# Swathi.net
KiCad netlist of a schematic drawn in EAGLE
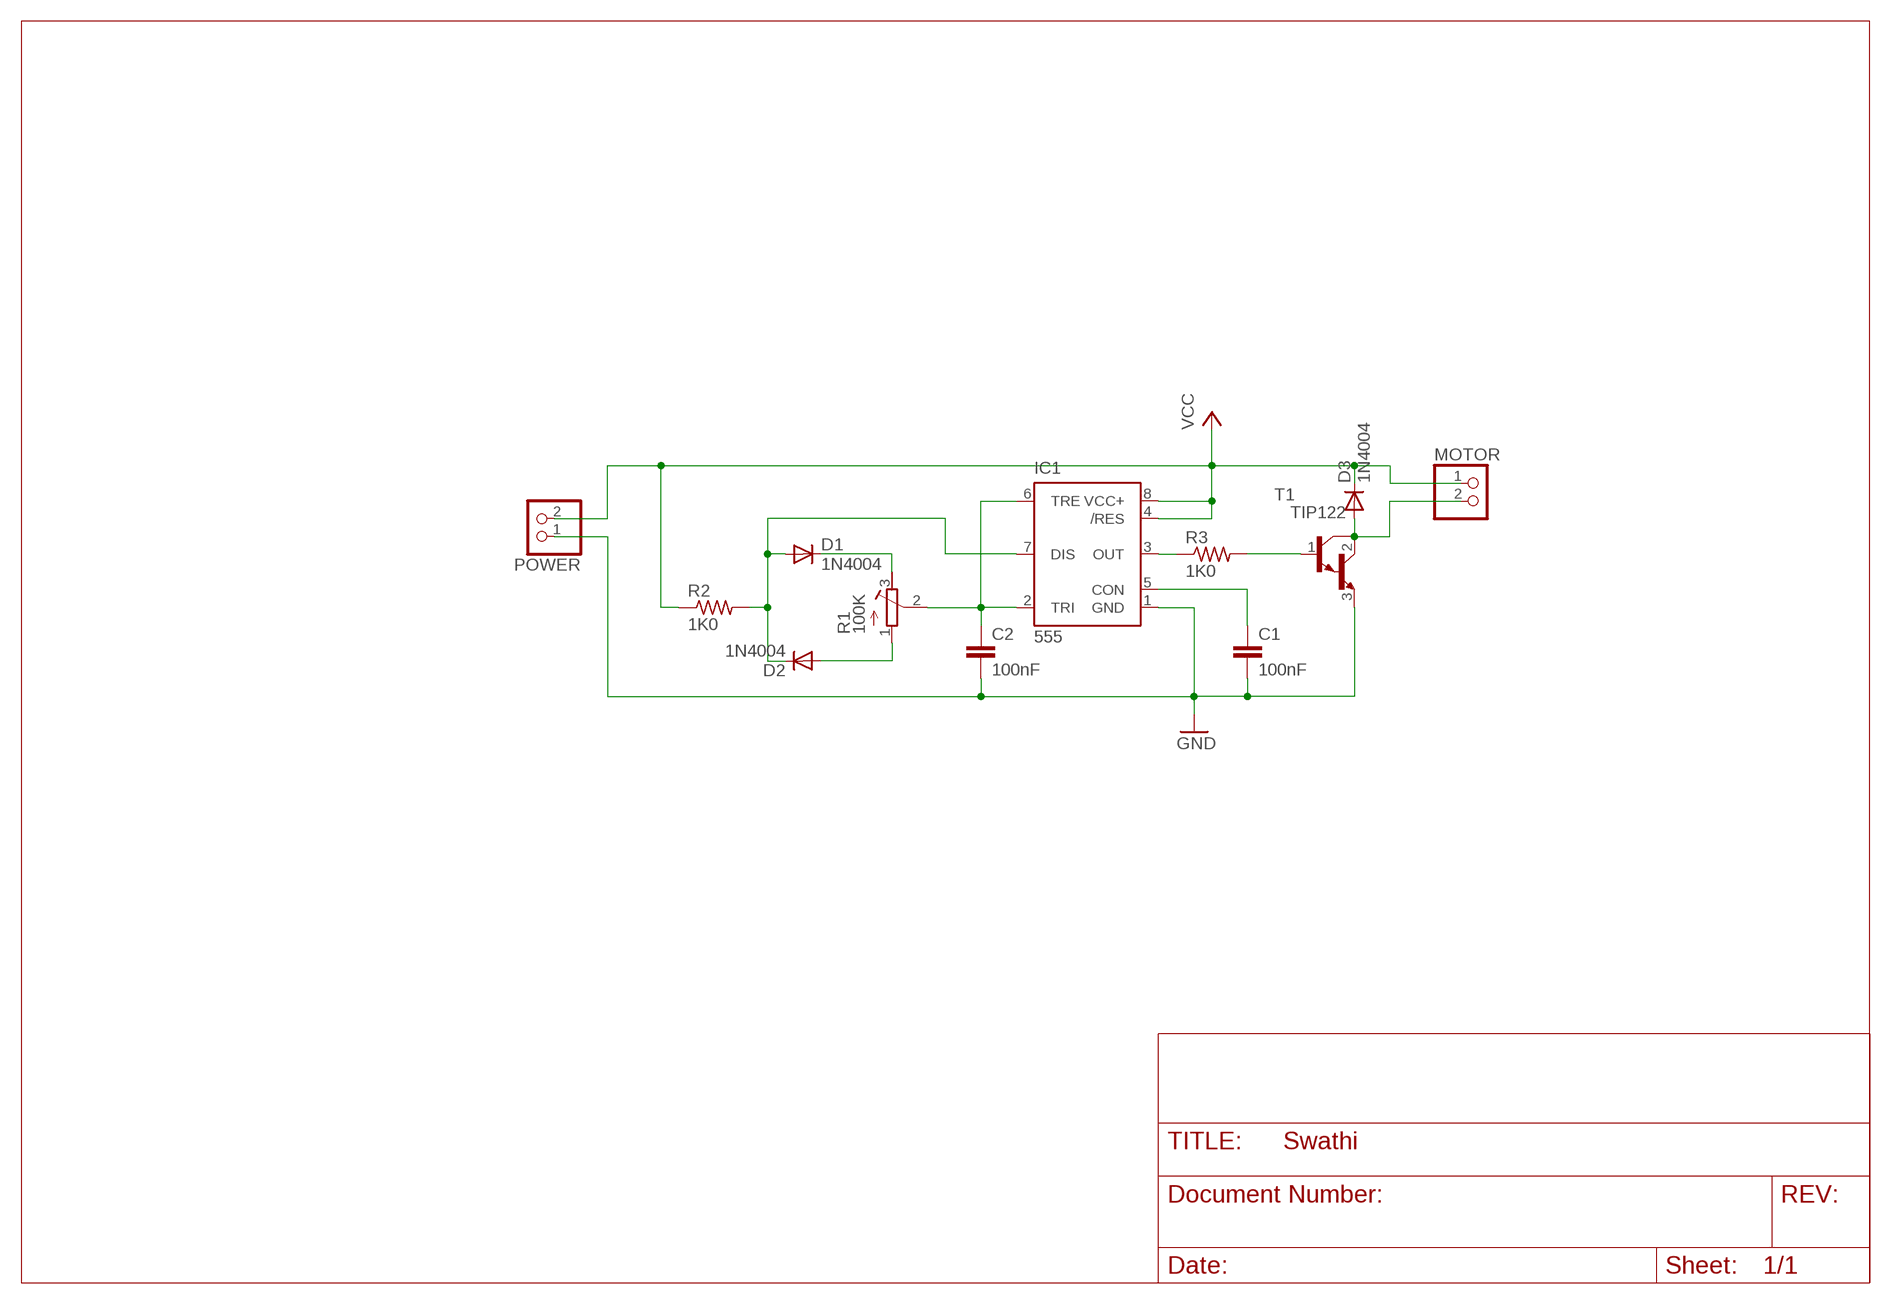
[diagram p0: schematic, sheet 1]

(export (version "E")
  (design (tool "Eeschema 10.0.6"))
  (components
    (comp (ref "C1")
      (value "100nF")
      (footprint "eagle-import:C025-025X050")
      (libsource (lib "eagle-import") (part "C-EU025-025X050"))
    )
    (comp (ref "C2")
      (value "100nF")
      (footprint "eagle-import:C025-025X050")
      (libsource (lib "eagle-import") (part "C-EU025-025X050"))
    )
    (comp (ref "D1")
      (value "1N4004")
      (footprint "eagle-import:DO41-10")
      (libsource (lib "eagle-import") (part "1N4004"))
    )
    (comp (ref "D2")
      (value "1N4004")
      (footprint "eagle-import:DO41-10")
      (libsource (lib "eagle-import") (part "1N4004"))
    )
    (comp (ref "D3")
      (value "1N4004")
      (footprint "eagle-import:DO41-10")
      (libsource (lib "eagle-import") (part "1N4004"))
    )
    (comp (ref "IC1")
      (value "555")
      (footprint "eagle-import:DIP08")
      (libsource (lib "eagle-import") (part "555P"))
    )
    (comp (ref "MOTOR")
      (value "PINHD-1X2")
      (footprint "eagle-import:1X02")
      (libsource (lib "eagle-import") (part "PINHD-1X2"))
    )
    (comp (ref "POWER")
      (value "PINHD-1X2")
      (footprint "eagle-import:1X02")
      (libsource (lib "eagle-import") (part "PINHD-1X2"))
    )
    (comp (ref "R1")
      (value "100K")
      (footprint "eagle-import:RTRIM64W")
      (libsource (lib "eagle-import") (part "R-TRIMM64W"))
    )
    (comp (ref "R2")
      (value "1K0")
      (footprint "eagle-import:0204_7")
      (libsource (lib "eagle-import") (part "R-US_0204/7"))
    )
    (comp (ref "R3")
      (value "1K0")
      (footprint "eagle-import:0204_7")
      (libsource (lib "eagle-import") (part "R-US_0204/7"))
    )
    (comp (ref "T1")
      (value "TIP122")
      (footprint "eagle-import:TO220")
      (libsource (lib "eagle-import") (part "TIP122"))
    )
  )
  (nets
    (net (code "1") (name "GND") (class "Default")
      (node (ref "C1") (pin "2") (pinfunction "2_2") (pintype "passive"))
      (node (ref "C2") (pin "2") (pinfunction "2_2") (pintype "passive"))
      (node (ref "IC1") (pin "1") (pinfunction "GND_1") (pintype "power_in"))
      (node (ref "POWER") (pin "1") (pinfunction "1_1") (pintype "passive"))
      (node (ref "T1") (pin "3") (pinfunction "E_3") (pintype "passive"))
    )
    (net (code "2") (name "Net-(IC1-CON)") (class "Default")
      (node (ref "C1") (pin "1") (pinfunction "1_1") (pintype "passive"))
      (node (ref "IC1") (pin "5") (pinfunction "CON_5") (pintype "input"))
    )
    (net (code "3") (name "Net-(IC1-DIS)") (class "Default")
      (node (ref "D1") (pin "A") (pinfunction "A_A") (pintype "passive"))
      (node (ref "D2") (pin "C") (pinfunction "C_C") (pintype "passive"))
      (node (ref "IC1") (pin "7") (pinfunction "DIS_7") (pintype "input"))
      (node (ref "R2") (pin "2") (pinfunction "2_2") (pintype "passive"))
    )
    (net (code "4") (name "Net-(IC1-OUT)") (class "Default")
      (node (ref "IC1") (pin "3") (pinfunction "OUT_3") (pintype "output"))
      (node (ref "R3") (pin "1") (pinfunction "1_1") (pintype "passive"))
    )
    (net (code "5") (name "Net-(IC1-TRE)") (class "Default")
      (node (ref "C2") (pin "1") (pinfunction "1_1") (pintype "passive"))
      (node (ref "IC1") (pin "2") (pinfunction "TRI_2") (pintype "input"))
      (node (ref "IC1") (pin "6") (pinfunction "TRE_6") (pintype "input"))
      (node (ref "R1") (pin "2") (pinfunction "S_2") (pintype "passive"))
    )
    (net (code "6") (name "Net-(R1-A)") (class "Default")
      (node (ref "D2") (pin "A") (pinfunction "A_A") (pintype "passive"))
      (node (ref "R1") (pin "1") (pinfunction "A_1") (pintype "passive"))
    )
    (net (code "7") (name "Net-(R1-E)") (class "Default")
      (node (ref "D1") (pin "C") (pinfunction "C_C") (pintype "passive"))
      (node (ref "R1") (pin "3") (pinfunction "E_3") (pintype "passive"))
    )
    (net (code "8") (name "Net-(T1-B)") (class "Default")
      (node (ref "R3") (pin "2") (pinfunction "2_2") (pintype "passive"))
      (node (ref "T1") (pin "1") (pinfunction "B_1") (pintype "passive"))
    )
    (net (code "9") (name "Net-(T1-C)") (class "Default")
      (node (ref "D3") (pin "A") (pinfunction "A_A") (pintype "passive"))
      (node (ref "MOTOR") (pin "2") (pinfunction "2_2") (pintype "passive"))
      (node (ref "T1") (pin "2") (pinfunction "C_2") (pintype "passive"))
    )
    (net (code "10") (name "VCC") (class "Default")
      (node (ref "D3") (pin "C") (pinfunction "C_C") (pintype "passive"))
      (node (ref "IC1") (pin "4") (pinfunction "/RES_4") (pintype "input"))
      (node (ref "IC1") (pin "8") (pinfunction "VCC+_8") (pintype "power_in"))
      (node (ref "MOTOR") (pin "1") (pinfunction "1_1") (pintype "passive"))
      (node (ref "POWER") (pin "2") (pinfunction "2_2") (pintype "passive"))
      (node (ref "R2") (pin "1") (pinfunction "1_1") (pintype "passive"))
    )
  )
)
